# FeedBack.net
KiCad netlist of a schematic drawn in EAGLE
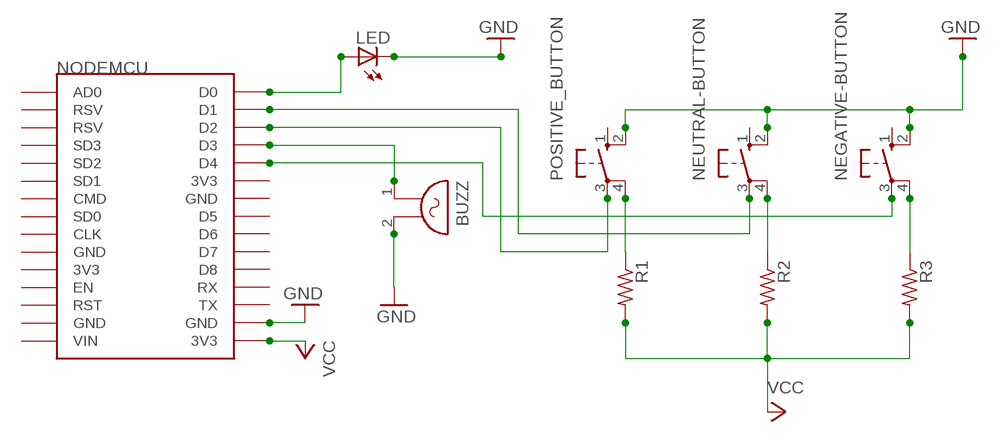
[diagram p0: schematic, sheet 1]

(export (version "E")
  (design (tool "Eeschema 10.0.6"))
  (components
    (comp (ref "BUZZ")
      (value "F/HGP")
      (footprint "eagle-import:F_HGP")
      (libsource (lib "eagle-import") (part "F/HGP"))
    )
    (comp (ref "LED")
      (value "LED3MM")
      (footprint "eagle-import:LED3MM")
      (libsource (lib "eagle-import") (part "LED3MM"))
    )
    (comp (ref "NEGATIVE-BUTTON")
      (value "10-XX")
      (footprint "eagle-import:B3F-10XX")
      (fields (field (name "MPN") "B3F-1000"))
      (libsource (lib "eagle-import") (part "10-XX"))
    )
    (comp (ref "NEUTRAL-BUTTON")
      (value "10-XX")
      (footprint "eagle-import:B3F-10XX")
      (fields (field (name "MPN") "B3F-1000"))
      (libsource (lib "eagle-import") (part "10-XX"))
    )
    (comp (ref "NODEMCU")
      (value "ESP12E_DEVKIT")
      (footprint "eagle-import:ESP12E_DEVKIT")
      (libsource (lib "eagle-import") (part "ESP12E_DEVKIT"))
    )
    (comp (ref "POSITIVE_BUTTON")
      (value "10-XX")
      (footprint "eagle-import:B3F-10XX")
      (fields (field (name "MPN") "B3F-1000"))
      (libsource (lib "eagle-import") (part "10-XX"))
    )
    (comp (ref "R1")
      (value "R-US_0204/5")
      (footprint "eagle-import:0204_5")
      (libsource (lib "eagle-import") (part "R-US_0204/5"))
    )
    (comp (ref "R2")
      (value "R-US_0204/5")
      (footprint "eagle-import:0204_5")
      (libsource (lib "eagle-import") (part "R-US_0204/5"))
    )
    (comp (ref "R3")
      (value "R-US_0204/5")
      (footprint "eagle-import:0204_5")
      (libsource (lib "eagle-import") (part "R-US_0204/5"))
    )
  )
  (nets
    (net (code "1") (name "GND") (class "Default")
      (node (ref "BUZZ") (pin "2") (pinfunction "2_2") (pintype "passive"))
      (node (ref "LED") (pin "K") (pinfunction "C_K") (pintype "passive"))
      (node (ref "NEGATIVE-BUTTON") (pin "2") (pinfunction "S1_2") (pintype "passive"))
      (node (ref "NEUTRAL-BUTTON") (pin "2") (pinfunction "S1_2") (pintype "passive"))
      (node (ref "NODEMCU") (pin "GND@3") (pinfunction "GND_GND@3") (pintype "bidirectional"))
      (node (ref "POSITIVE_BUTTON") (pin "2") (pinfunction "S1_2") (pintype "passive"))
    )
    (net (code "2") (name "Net-(BUZZ-Pad1)") (class "Default")
      (node (ref "BUZZ") (pin "1") (pinfunction "1_1") (pintype "passive"))
      (node (ref "NODEMCU") (pin "D3") (pinfunction "D3_D3") (pintype "bidirectional"))
    )
    (net (code "3") (name "Net-(LED-PadA)") (class "Default")
      (node (ref "LED") (pin "A") (pinfunction "A_A") (pintype "passive"))
      (node (ref "NODEMCU") (pin "D0") (pinfunction "D0_D0") (pintype "bidirectional"))
    )
    (net (code "4") (name "Net-(NEGATIVE-BUTTON-P)") (class "Default")
      (node (ref "NEGATIVE-BUTTON") (pin "3") (pinfunction "P_3") (pintype "passive"))
      (node (ref "NODEMCU") (pin "D4") (pinfunction "D4_D4") (pintype "bidirectional"))
    )
    (net (code "5") (name "Net-(NEGATIVE-BUTTON-P1)") (class "Default")
      (node (ref "NEGATIVE-BUTTON") (pin "4") (pinfunction "P1_4") (pintype "passive"))
      (node (ref "R3") (pin "1") (pinfunction "1_1") (pintype "passive"))
    )
    (net (code "6") (name "Net-(NEUTRAL-BUTTON-P)") (class "Default")
      (node (ref "NEUTRAL-BUTTON") (pin "3") (pinfunction "P_3") (pintype "passive"))
      (node (ref "NODEMCU") (pin "D1") (pinfunction "D1_D1") (pintype "bidirectional"))
    )
    (net (code "7") (name "Net-(NEUTRAL-BUTTON-P1)") (class "Default")
      (node (ref "NEUTRAL-BUTTON") (pin "4") (pinfunction "P1_4") (pintype "passive"))
      (node (ref "R2") (pin "1") (pinfunction "1_1") (pintype "passive"))
    )
    (net (code "8") (name "Net-(POSITIVE_BUTTON-P)") (class "Default")
      (node (ref "NODEMCU") (pin "D2") (pinfunction "D2_D2") (pintype "bidirectional"))
      (node (ref "POSITIVE_BUTTON") (pin "3") (pinfunction "P_3") (pintype "passive"))
    )
    (net (code "9") (name "Net-(POSITIVE_BUTTON-P1)") (class "Default")
      (node (ref "POSITIVE_BUTTON") (pin "4") (pinfunction "P1_4") (pintype "passive"))
      (node (ref "R1") (pin "1") (pinfunction "1_1") (pintype "passive"))
    )
    (net (code "10") (name "VCC") (class "Default")
      (node (ref "NODEMCU") (pin "3V3@2") (pinfunction "3V3_3V3@2") (pintype "bidirectional"))
      (node (ref "R1") (pin "2") (pinfunction "2_2") (pintype "passive"))
      (node (ref "R2") (pin "2") (pinfunction "2_2") (pintype "passive"))
      (node (ref "R3") (pin "2") (pinfunction "2_2") (pintype "passive"))
    )
    (net (code "11") (name "unconnected-(NEGATIVE-BUTTON-S-Pad1)") (class "Default")
      (node (ref "NEGATIVE-BUTTON") (pin "1") (pinfunction "S_1") (pintype "passive"))
    )
    (net (code "12") (name "unconnected-(NEUTRAL-BUTTON-S-Pad1)") (class "Default")
      (node (ref "NEUTRAL-BUTTON") (pin "1") (pinfunction "S_1") (pintype "passive"))
    )
    (net (code "13") (name "unconnected-(NODEMCU-3V3-Pad3V3@0)") (class "Default")
      (node (ref "NODEMCU") (pin "3V3@0") (pinfunction "3V3_3V3@0") (pintype "bidirectional"))
    )
    (net (code "14") (name "unconnected-(NODEMCU-3V3-Pad3V3@1)") (class "Default")
      (node (ref "NODEMCU") (pin "3V3@1") (pinfunction "3V3_3V3@1") (pintype "bidirectional"))
    )
    (net (code "15") (name "unconnected-(NODEMCU-GND-PadGND@0)") (class "Default")
      (node (ref "NODEMCU") (pin "GND@0") (pinfunction "GND_GND@0") (pintype "bidirectional"))
    )
    (net (code "16") (name "unconnected-(NODEMCU-GND-PadGND@1)") (class "Default")
      (node (ref "NODEMCU") (pin "GND@1") (pinfunction "GND_GND@1") (pintype "bidirectional"))
    )
    (net (code "17") (name "unconnected-(NODEMCU-GND-PadGND@2)") (class "Default")
      (node (ref "NODEMCU") (pin "GND@2") (pinfunction "GND_GND@2") (pintype "bidirectional"))
    )
    (net (code "18") (name "unconnected-(NODEMCU-PadAD0)") (class "Default")
      (node (ref "NODEMCU") (pin "AD0") (pinfunction "AD0_AD0") (pintype "bidirectional"))
    )
    (net (code "19") (name "unconnected-(NODEMCU-PadCLK)") (class "Default")
      (node (ref "NODEMCU") (pin "CLK") (pinfunction "CLK_CLK") (pintype "bidirectional"))
    )
    (net (code "20") (name "unconnected-(NODEMCU-PadCMD)") (class "Default")
      (node (ref "NODEMCU") (pin "CMD") (pinfunction "CMD_CMD") (pintype "bidirectional"))
    )
    (net (code "21") (name "unconnected-(NODEMCU-PadD5)") (class "Default")
      (node (ref "NODEMCU") (pin "D5") (pinfunction "D5_D5") (pintype "bidirectional"))
    )
    (net (code "22") (name "unconnected-(NODEMCU-PadD6)") (class "Default")
      (node (ref "NODEMCU") (pin "D6") (pinfunction "D6_D6") (pintype "bidirectional"))
    )
    (net (code "23") (name "unconnected-(NODEMCU-PadD7)") (class "Default")
      (node (ref "NODEMCU") (pin "D7") (pinfunction "D7_D7") (pintype "bidirectional"))
    )
    (net (code "24") (name "unconnected-(NODEMCU-PadD8)") (class "Default")
      (node (ref "NODEMCU") (pin "D8") (pinfunction "D8_D8") (pintype "bidirectional"))
    )
    (net (code "25") (name "unconnected-(NODEMCU-PadEN)") (class "Default")
      (node (ref "NODEMCU") (pin "EN") (pinfunction "EN_EN") (pintype "bidirectional"))
    )
    (net (code "26") (name "unconnected-(NODEMCU-PadRST)") (class "Default")
      (node (ref "NODEMCU") (pin "RST") (pinfunction "RST_RST") (pintype "bidirectional"))
    )
    (net (code "27") (name "unconnected-(NODEMCU-PadRX)") (class "Default")
      (node (ref "NODEMCU") (pin "RX") (pinfunction "RX_RX") (pintype "bidirectional"))
    )
    (net (code "28") (name "unconnected-(NODEMCU-PadSD0)") (class "Default")
      (node (ref "NODEMCU") (pin "SD0") (pinfunction "SD0_SD0") (pintype "bidirectional"))
    )
    (net (code "29") (name "unconnected-(NODEMCU-PadSD1)") (class "Default")
      (node (ref "NODEMCU") (pin "SD1") (pinfunction "SD1_SD1") (pintype "bidirectional"))
    )
    (net (code "30") (name "unconnected-(NODEMCU-PadSD2)") (class "Default")
      (node (ref "NODEMCU") (pin "SD2") (pinfunction "SD2_SD2") (pintype "bidirectional"))
    )
    (net (code "31") (name "unconnected-(NODEMCU-PadSD3)") (class "Default")
      (node (ref "NODEMCU") (pin "SD3") (pinfunction "SD3_SD3") (pintype "bidirectional"))
    )
    (net (code "32") (name "unconnected-(NODEMCU-PadTX)") (class "Default")
      (node (ref "NODEMCU") (pin "TX") (pinfunction "TX_TX") (pintype "bidirectional"))
    )
    (net (code "33") (name "unconnected-(NODEMCU-PadVIN)") (class "Default")
      (node (ref "NODEMCU") (pin "VIN") (pinfunction "VIN_VIN") (pintype "bidirectional"))
    )
    (net (code "34") (name "unconnected-(NODEMCU-RSV-PadRSV@0)") (class "Default")
      (node (ref "NODEMCU") (pin "RSV@0") (pinfunction "RSV_RSV@0") (pintype "bidirectional"))
    )
    (net (code "35") (name "unconnected-(NODEMCU-RSV-PadRSV@1)") (class "Default")
      (node (ref "NODEMCU") (pin "RSV@1") (pinfunction "RSV_RSV@1") (pintype "bidirectional"))
    )
    (net (code "36") (name "unconnected-(POSITIVE_BUTTON-S-Pad1)") (class "Default")
      (node (ref "POSITIVE_BUTTON") (pin "1") (pinfunction "S_1") (pintype "passive"))
    )
  )
)
